# core_XX4_THT.net
KiCad netlist of a schematic drawn in EAGLE
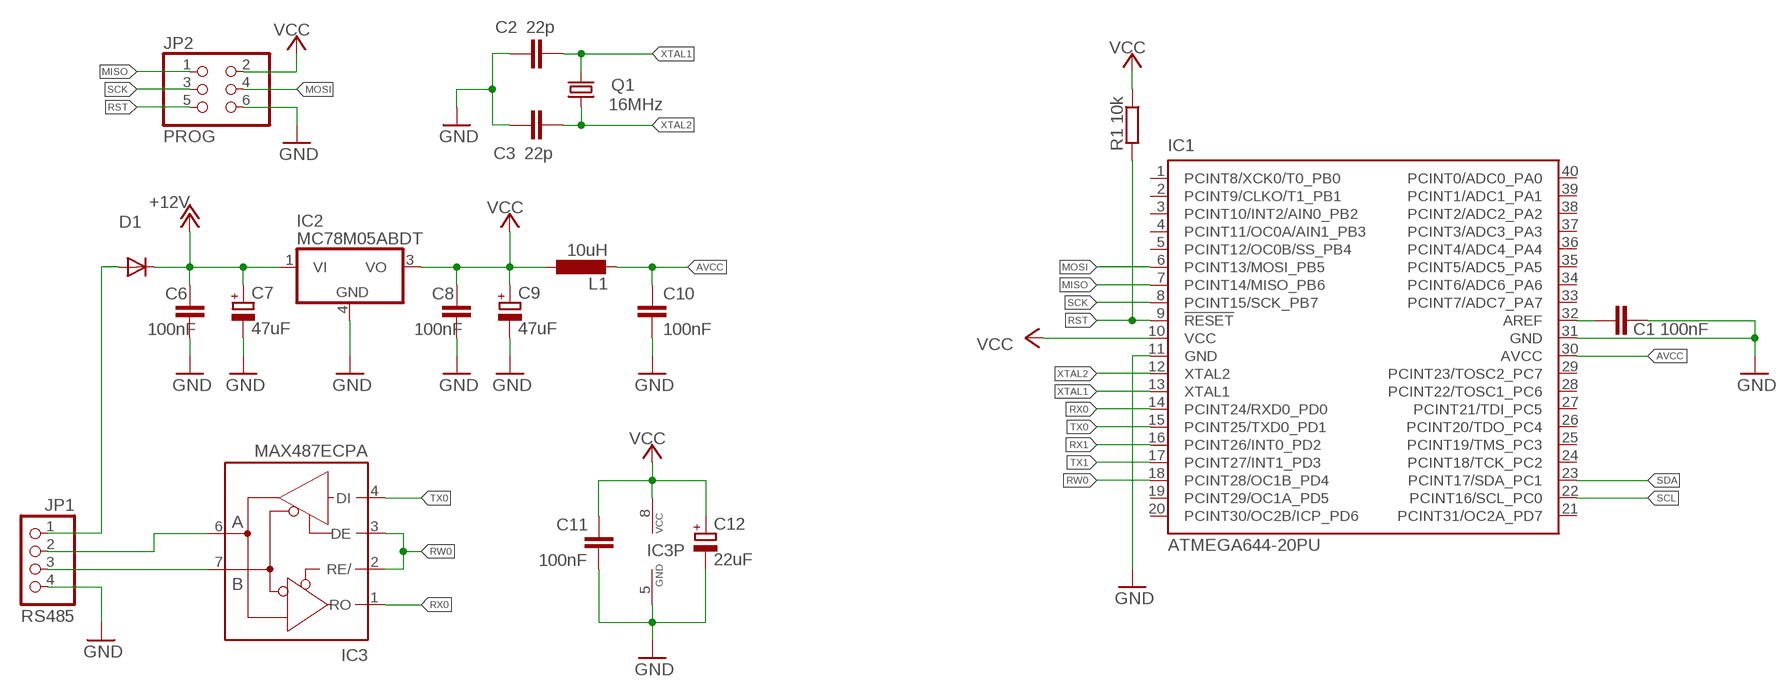
[diagram p0: schematic, sheet 1]

(export (version "E")
  (design (tool "Eeschema 10.0.6"))
  (components
    (comp (ref "C1")
      (value "100nF")
      (footprint "eagle-import:C025-025X050")
      (libsource (lib "eagle-import") (part "C-EU025-025X050"))
    )
    (comp (ref "C2")
      (value "22p")
      (footprint "eagle-import:C025-024X044")
      (libsource (lib "eagle-import") (part "C-EU025-024X044"))
    )
    (comp (ref "C3")
      (value "22p")
      (footprint "eagle-import:C025-024X044")
      (libsource (lib "eagle-import") (part "C-EU025-024X044"))
    )
    (comp (ref "C6")
      (value "100nF")
      (footprint "eagle-import:C025-025X050")
      (libsource (lib "eagle-import") (part "C-EU025-025X050"))
    )
    (comp (ref "C7")
      (value "47uF")
      (footprint "eagle-import:E2,5-6")
      (libsource (lib "eagle-import") (part "CPOL-EUE2.5-6"))
    )
    (comp (ref "C8")
      (value "100nF")
      (footprint "eagle-import:C025-025X050")
      (libsource (lib "eagle-import") (part "C-EU025-025X050"))
    )
    (comp (ref "C9")
      (value "47uF")
      (footprint "eagle-import:E2,5-6")
      (libsource (lib "eagle-import") (part "CPOL-EUE2.5-6"))
    )
    (comp (ref "C10")
      (value "100nF")
      (footprint "eagle-import:C025-025X050")
      (libsource (lib "eagle-import") (part "C-EU025-025X050"))
    )
    (comp (ref "C11")
      (value "100nF")
      (footprint "eagle-import:C025-025X050")
      (libsource (lib "eagle-import") (part "C-EU025-025X050"))
    )
    (comp (ref "C12")
      (value "22uF")
      (footprint "eagle-import:E2-5")
      (libsource (lib "eagle-import") (part "CPOL-EUE2-5"))
    )
    (comp (ref "D1")
      (value "1N4002")
      (footprint "eagle-import:DO34-7")
      (libsource (lib "eagle-import") (part "BAS15"))
    )
    (comp (ref "IC1")
      (value "ATMEGA644-20PU")
      (footprint "eagle-import:DIL40")
      (libsource (lib "eagle-import") (part "ATMEGA644-PU20"))
    )
    (comp (ref "IC2")
      (value "MC78M05ABDT")
      (footprint "eagle-import:DPACK_3")
      (libsource (lib "eagle-import") (part "MC78M05ABDT"))
    )
    (comp (ref "IC3")
      (value "MAX487ECPA")
      (footprint "eagle-import:DIL08")
      (fields (field (name "MPN") "MAX481CPA+"))
      (libsource (lib "eagle-import") (part "MAX481CPA"))
    )
    (comp (ref "JP1")
      (value "RS485")
      (footprint "eagle-import:1X04")
      (libsource (lib "eagle-import") (part "PINHD-1X4"))
    )
    (comp (ref "JP2")
      (value "PROG")
      (footprint "eagle-import:2X03")
      (libsource (lib "eagle-import") (part "PINHD-2X3"))
    )
    (comp (ref "L1")
      (value "10uH")
      (footprint "eagle-import:0207_12")
      (libsource (lib "eagle-import") (part "L-EU0207/12"))
    )
    (comp (ref "Q1")
      (value "16MHz")
      (footprint "eagle-import:HC49_S")
      (libsource (lib "eagle-import") (part "CRYSTALHC49S"))
    )
    (comp (ref "R1")
      (value "10k")
      (footprint "eagle-import:0204V")
      (libsource (lib "eagle-import") (part "R-EU_0204/2V"))
    )
  )
  (nets
    (net (code "1") (name "+12V") (class "Default")
      (node (ref "C6") (pin "1") (pinfunction "1_1") (pintype "passive"))
      (node (ref "C7") (pin "+") (pinfunction "+_+") (pintype "passive"))
      (node (ref "D1") (pin "C") (pinfunction "C_C") (pintype "passive"))
      (node (ref "IC2") (pin "1") (pinfunction "VI_1") (pintype "input"))
    )
    (net (code "2") (name "AVCC") (class "Default")
      (node (ref "C10") (pin "1") (pinfunction "1_1") (pintype "passive"))
      (node (ref "IC1") (pin "30") (pinfunction "AVCC_30") (pintype "power_in"))
      (node (ref "L1") (pin "2") (pinfunction "2_2") (pintype "passive"))
    )
    (net (code "3") (name "GND") (class "Default")
      (node (ref "C1") (pin "2") (pinfunction "2_2") (pintype "passive"))
      (node (ref "C10") (pin "2") (pinfunction "2_2") (pintype "passive"))
      (node (ref "C11") (pin "2") (pinfunction "2_2") (pintype "passive"))
      (node (ref "C12") (pin "-") (pinfunction "-_-") (pintype "passive"))
      (node (ref "C2") (pin "1") (pinfunction "1_1") (pintype "passive"))
      (node (ref "C3") (pin "1") (pinfunction "1_1") (pintype "passive"))
      (node (ref "C6") (pin "2") (pinfunction "2_2") (pintype "passive"))
      (node (ref "C7") (pin "-") (pinfunction "-_-") (pintype "passive"))
      (node (ref "C8") (pin "2") (pinfunction "2_2") (pintype "passive"))
      (node (ref "C9") (pin "-") (pinfunction "-_-") (pintype "passive"))
      (node (ref "IC1") (pin "11") (pinfunction "GND_11") (pintype "power_in"))
      (node (ref "IC1") (pin "31") (pinfunction "GND_31") (pintype "power_in"))
      (node (ref "IC2") (pin "4") (pinfunction "GND_4") (pintype "passive"))
      (node (ref "IC3") (pin "5") (pinfunction "GND_5") (pintype "power_in"))
      (node (ref "JP1") (pin "4") (pinfunction "4_4") (pintype "passive"))
      (node (ref "JP2") (pin "6") (pinfunction "6_6") (pintype "passive"))
    )
    (net (code "4") (name "MISO") (class "Default")
      (node (ref "IC1") (pin "7") (pinfunction "PCINT14/MISO_PB6_7") (pintype "bidirectional"))
      (node (ref "JP2") (pin "1") (pinfunction "1_1") (pintype "passive"))
    )
    (net (code "5") (name "MOSI") (class "Default")
      (node (ref "IC1") (pin "6") (pinfunction "PCINT13/MOSI_PB5_6") (pintype "bidirectional"))
      (node (ref "JP2") (pin "4") (pinfunction "4_4") (pintype "passive"))
    )
    (net (code "6") (name "Net-(D1-PadA)") (class "Default")
      (node (ref "D1") (pin "A") (pinfunction "A_A") (pintype "passive"))
      (node (ref "JP1") (pin "1") (pinfunction "1_1") (pintype "passive"))
    )
    (net (code "7") (name "Net-(IC1-AREF)") (class "Default")
      (node (ref "C1") (pin "1") (pinfunction "1_1") (pintype "passive"))
      (node (ref "IC1") (pin "32") (pinfunction "AREF_32") (pintype "passive"))
    )
    (net (code "8") (name "Net-(IC3A-A)") (class "Default")
      (node (ref "IC3") (pin "6") (pinfunction "A_6") (pintype "passive"))
      (node (ref "JP1") (pin "2") (pinfunction "2_2") (pintype "passive"))
    )
    (net (code "9") (name "Net-(IC3A-B)") (class "Default")
      (node (ref "IC3") (pin "7") (pinfunction "B_7") (pintype "passive"))
      (node (ref "JP1") (pin "3") (pinfunction "3_3") (pintype "passive"))
    )
    (net (code "10") (name "RST") (class "Default")
      (node (ref "IC1") (pin "9") (pinfunction "~{RESET}_9") (pintype "input"))
      (node (ref "JP2") (pin "5") (pinfunction "5_5") (pintype "passive"))
      (node (ref "R1") (pin "2") (pinfunction "2_2") (pintype "passive"))
    )
    (net (code "11") (name "RW0") (class "Default")
      (node (ref "IC1") (pin "18") (pinfunction "PCINT28/OC1B_PD4_18") (pintype "bidirectional"))
      (node (ref "IC3") (pin "2") (pinfunction "RE/_2") (pintype "input"))
      (node (ref "IC3") (pin "3") (pinfunction "DE_3") (pintype "input"))
    )
    (net (code "12") (name "RX0") (class "Default")
      (node (ref "IC1") (pin "14") (pinfunction "PCINT24/RXD0_PD0_14") (pintype "bidirectional"))
      (node (ref "IC3") (pin "1") (pinfunction "RO_1") (pintype "output"))
    )
    (net (code "13") (name "RX1") (class "Default")
      (node (ref "IC1") (pin "16") (pinfunction "PCINT26/INT0_PD2_16") (pintype "bidirectional"))
    )
    (net (code "14") (name "SCK") (class "Default")
      (node (ref "IC1") (pin "8") (pinfunction "PCINT15/SCK_PB7_8") (pintype "bidirectional"))
      (node (ref "JP2") (pin "3") (pinfunction "3_3") (pintype "passive"))
    )
    (net (code "15") (name "SCL") (class "Default")
      (node (ref "IC1") (pin "22") (pinfunction "PCINT16/SCL_PC0_22") (pintype "bidirectional"))
    )
    (net (code "16") (name "SDA") (class "Default")
      (node (ref "IC1") (pin "23") (pinfunction "PCINT17/SDA_PC1_23") (pintype "bidirectional"))
    )
    (net (code "17") (name "TX0") (class "Default")
      (node (ref "IC1") (pin "15") (pinfunction "PCINT25/TXD0_PD1_15") (pintype "bidirectional"))
      (node (ref "IC3") (pin "4") (pinfunction "DI_4") (pintype "input"))
    )
    (net (code "18") (name "TX1") (class "Default")
      (node (ref "IC1") (pin "17") (pinfunction "PCINT27/INT1_PD3_17") (pintype "bidirectional"))
    )
    (net (code "19") (name "VCC") (class "Default")
      (node (ref "C11") (pin "1") (pinfunction "1_1") (pintype "passive"))
      (node (ref "C12") (pin "+") (pinfunction "+_+") (pintype "passive"))
      (node (ref "C8") (pin "1") (pinfunction "1_1") (pintype "passive"))
      (node (ref "C9") (pin "+") (pinfunction "+_+") (pintype "passive"))
      (node (ref "IC1") (pin "10") (pinfunction "VCC_10") (pintype "power_in"))
      (node (ref "IC2") (pin "3") (pinfunction "VO_3") (pintype "passive"))
      (node (ref "IC3") (pin "8") (pinfunction "VCC_8") (pintype "power_in"))
      (node (ref "JP2") (pin "2") (pinfunction "2_2") (pintype "passive"))
      (node (ref "L1") (pin "1") (pinfunction "1_1") (pintype "passive"))
      (node (ref "R1") (pin "1") (pinfunction "1_1") (pintype "passive"))
    )
    (net (code "20") (name "XTAL1") (class "Default")
      (node (ref "C2") (pin "2") (pinfunction "2_2") (pintype "passive"))
      (node (ref "IC1") (pin "13") (pinfunction "XTAL1_13") (pintype "input"))
      (node (ref "Q1") (pin "2") (pinfunction "2_2") (pintype "passive"))
    )
    (net (code "21") (name "XTAL2") (class "Default")
      (node (ref "C3") (pin "2") (pinfunction "2_2") (pintype "passive"))
      (node (ref "IC1") (pin "12") (pinfunction "XTAL2_12") (pintype "output"))
      (node (ref "Q1") (pin "1") (pinfunction "1_1") (pintype "passive"))
    )
    (net (code "22") (name "unconnected-(IC1-PCINT0{slash}ADC0_PA0-Pad40)") (class "Default")
      (node (ref "IC1") (pin "40") (pinfunction "PCINT0/ADC0_PA0_40") (pintype "bidirectional"))
    )
    (net (code "23") (name "unconnected-(IC1-PCINT1{slash}ADC1_PA1-Pad39)") (class "Default")
      (node (ref "IC1") (pin "39") (pinfunction "PCINT1/ADC1_PA1_39") (pintype "bidirectional"))
    )
    (net (code "24") (name "unconnected-(IC1-PCINT2{slash}ADC2_PA2-Pad38)") (class "Default")
      (node (ref "IC1") (pin "38") (pinfunction "PCINT2/ADC2_PA2_38") (pintype "bidirectional"))
    )
    (net (code "25") (name "unconnected-(IC1-PCINT3{slash}ADC3_PA3-Pad37)") (class "Default")
      (node (ref "IC1") (pin "37") (pinfunction "PCINT3/ADC3_PA3_37") (pintype "bidirectional"))
    )
    (net (code "26") (name "unconnected-(IC1-PCINT4{slash}ADC4_PA4-Pad36)") (class "Default")
      (node (ref "IC1") (pin "36") (pinfunction "PCINT4/ADC4_PA4_36") (pintype "bidirectional"))
    )
    (net (code "27") (name "unconnected-(IC1-PCINT5{slash}ADC5_PA5-Pad35)") (class "Default")
      (node (ref "IC1") (pin "35") (pinfunction "PCINT5/ADC5_PA5_35") (pintype "bidirectional"))
    )
    (net (code "28") (name "unconnected-(IC1-PCINT6{slash}ADC6_PA6-Pad34)") (class "Default")
      (node (ref "IC1") (pin "34") (pinfunction "PCINT6/ADC6_PA6_34") (pintype "bidirectional"))
    )
    (net (code "29") (name "unconnected-(IC1-PCINT7{slash}ADC7_PA7-Pad33)") (class "Default")
      (node (ref "IC1") (pin "33") (pinfunction "PCINT7/ADC7_PA7_33") (pintype "bidirectional"))
    )
    (net (code "30") (name "unconnected-(IC1-PCINT8{slash}XCK0{slash}T0_PB0-Pad1)") (class "Default")
      (node (ref "IC1") (pin "1") (pinfunction "PCINT8/XCK0/T0_PB0_1") (pintype "bidirectional"))
    )
    (net (code "31") (name "unconnected-(IC1-PCINT9{slash}CLKO{slash}T1_PB1-Pad2)") (class "Default")
      (node (ref "IC1") (pin "2") (pinfunction "PCINT9/CLKO/T1_PB1_2") (pintype "bidirectional"))
    )
    (net (code "32") (name "unconnected-(IC1-PCINT10{slash}INT2{slash}AIN0_PB2-Pad3)") (class "Default")
      (node (ref "IC1") (pin "3") (pinfunction "PCINT10/INT2/AIN0_PB2_3") (pintype "bidirectional"))
    )
    (net (code "33") (name "unconnected-(IC1-PCINT11{slash}OC0A{slash}AIN1_PB3-Pad4)") (class "Default")
      (node (ref "IC1") (pin "4") (pinfunction "PCINT11/OC0A/AIN1_PB3_4") (pintype "bidirectional"))
    )
    (net (code "34") (name "unconnected-(IC1-PCINT12{slash}OC0B{slash}SS_PB4-Pad5)") (class "Default")
      (node (ref "IC1") (pin "5") (pinfunction "PCINT12/OC0B/SS_PB4_5") (pintype "bidirectional"))
    )
    (net (code "35") (name "unconnected-(IC1-PCINT18{slash}TCK_PC2-Pad24)") (class "Default")
      (node (ref "IC1") (pin "24") (pinfunction "PCINT18/TCK_PC2_24") (pintype "bidirectional"))
    )
    (net (code "36") (name "unconnected-(IC1-PCINT19{slash}TMS_PC3-Pad25)") (class "Default")
      (node (ref "IC1") (pin "25") (pinfunction "PCINT19/TMS_PC3_25") (pintype "bidirectional"))
    )
    (net (code "37") (name "unconnected-(IC1-PCINT20{slash}TDO_PC4-Pad26)") (class "Default")
      (node (ref "IC1") (pin "26") (pinfunction "PCINT20/TDO_PC4_26") (pintype "bidirectional"))
    )
    (net (code "38") (name "unconnected-(IC1-PCINT21{slash}TDI_PC5-Pad27)") (class "Default")
      (node (ref "IC1") (pin "27") (pinfunction "PCINT21/TDI_PC5_27") (pintype "bidirectional"))
    )
    (net (code "39") (name "unconnected-(IC1-PCINT22{slash}TOSC1_PC6-Pad28)") (class "Default")
      (node (ref "IC1") (pin "28") (pinfunction "PCINT22/TOSC1_PC6_28") (pintype "bidirectional"))
    )
    (net (code "40") (name "unconnected-(IC1-PCINT23{slash}TOSC2_PC7-Pad29)") (class "Default")
      (node (ref "IC1") (pin "29") (pinfunction "PCINT23/TOSC2_PC7_29") (pintype "bidirectional"))
    )
    (net (code "41") (name "unconnected-(IC1-PCINT29{slash}OC1A_PD5-Pad19)") (class "Default")
      (node (ref "IC1") (pin "19") (pinfunction "PCINT29/OC1A_PD5_19") (pintype "bidirectional"))
    )
    (net (code "42") (name "unconnected-(IC1-PCINT30{slash}OC2B{slash}ICP_PD6-Pad20)") (class "Default")
      (node (ref "IC1") (pin "20") (pinfunction "PCINT30/OC2B/ICP_PD6_20") (pintype "bidirectional"))
    )
    (net (code "43") (name "unconnected-(IC1-PCINT31{slash}OC2A_PD7-Pad21)") (class "Default")
      (node (ref "IC1") (pin "21") (pinfunction "PCINT31/OC2A_PD7_21") (pintype "bidirectional"))
    )
  )
)
